# RPLidar_interface.net
KiCad netlist of a schematic drawn in EAGLE
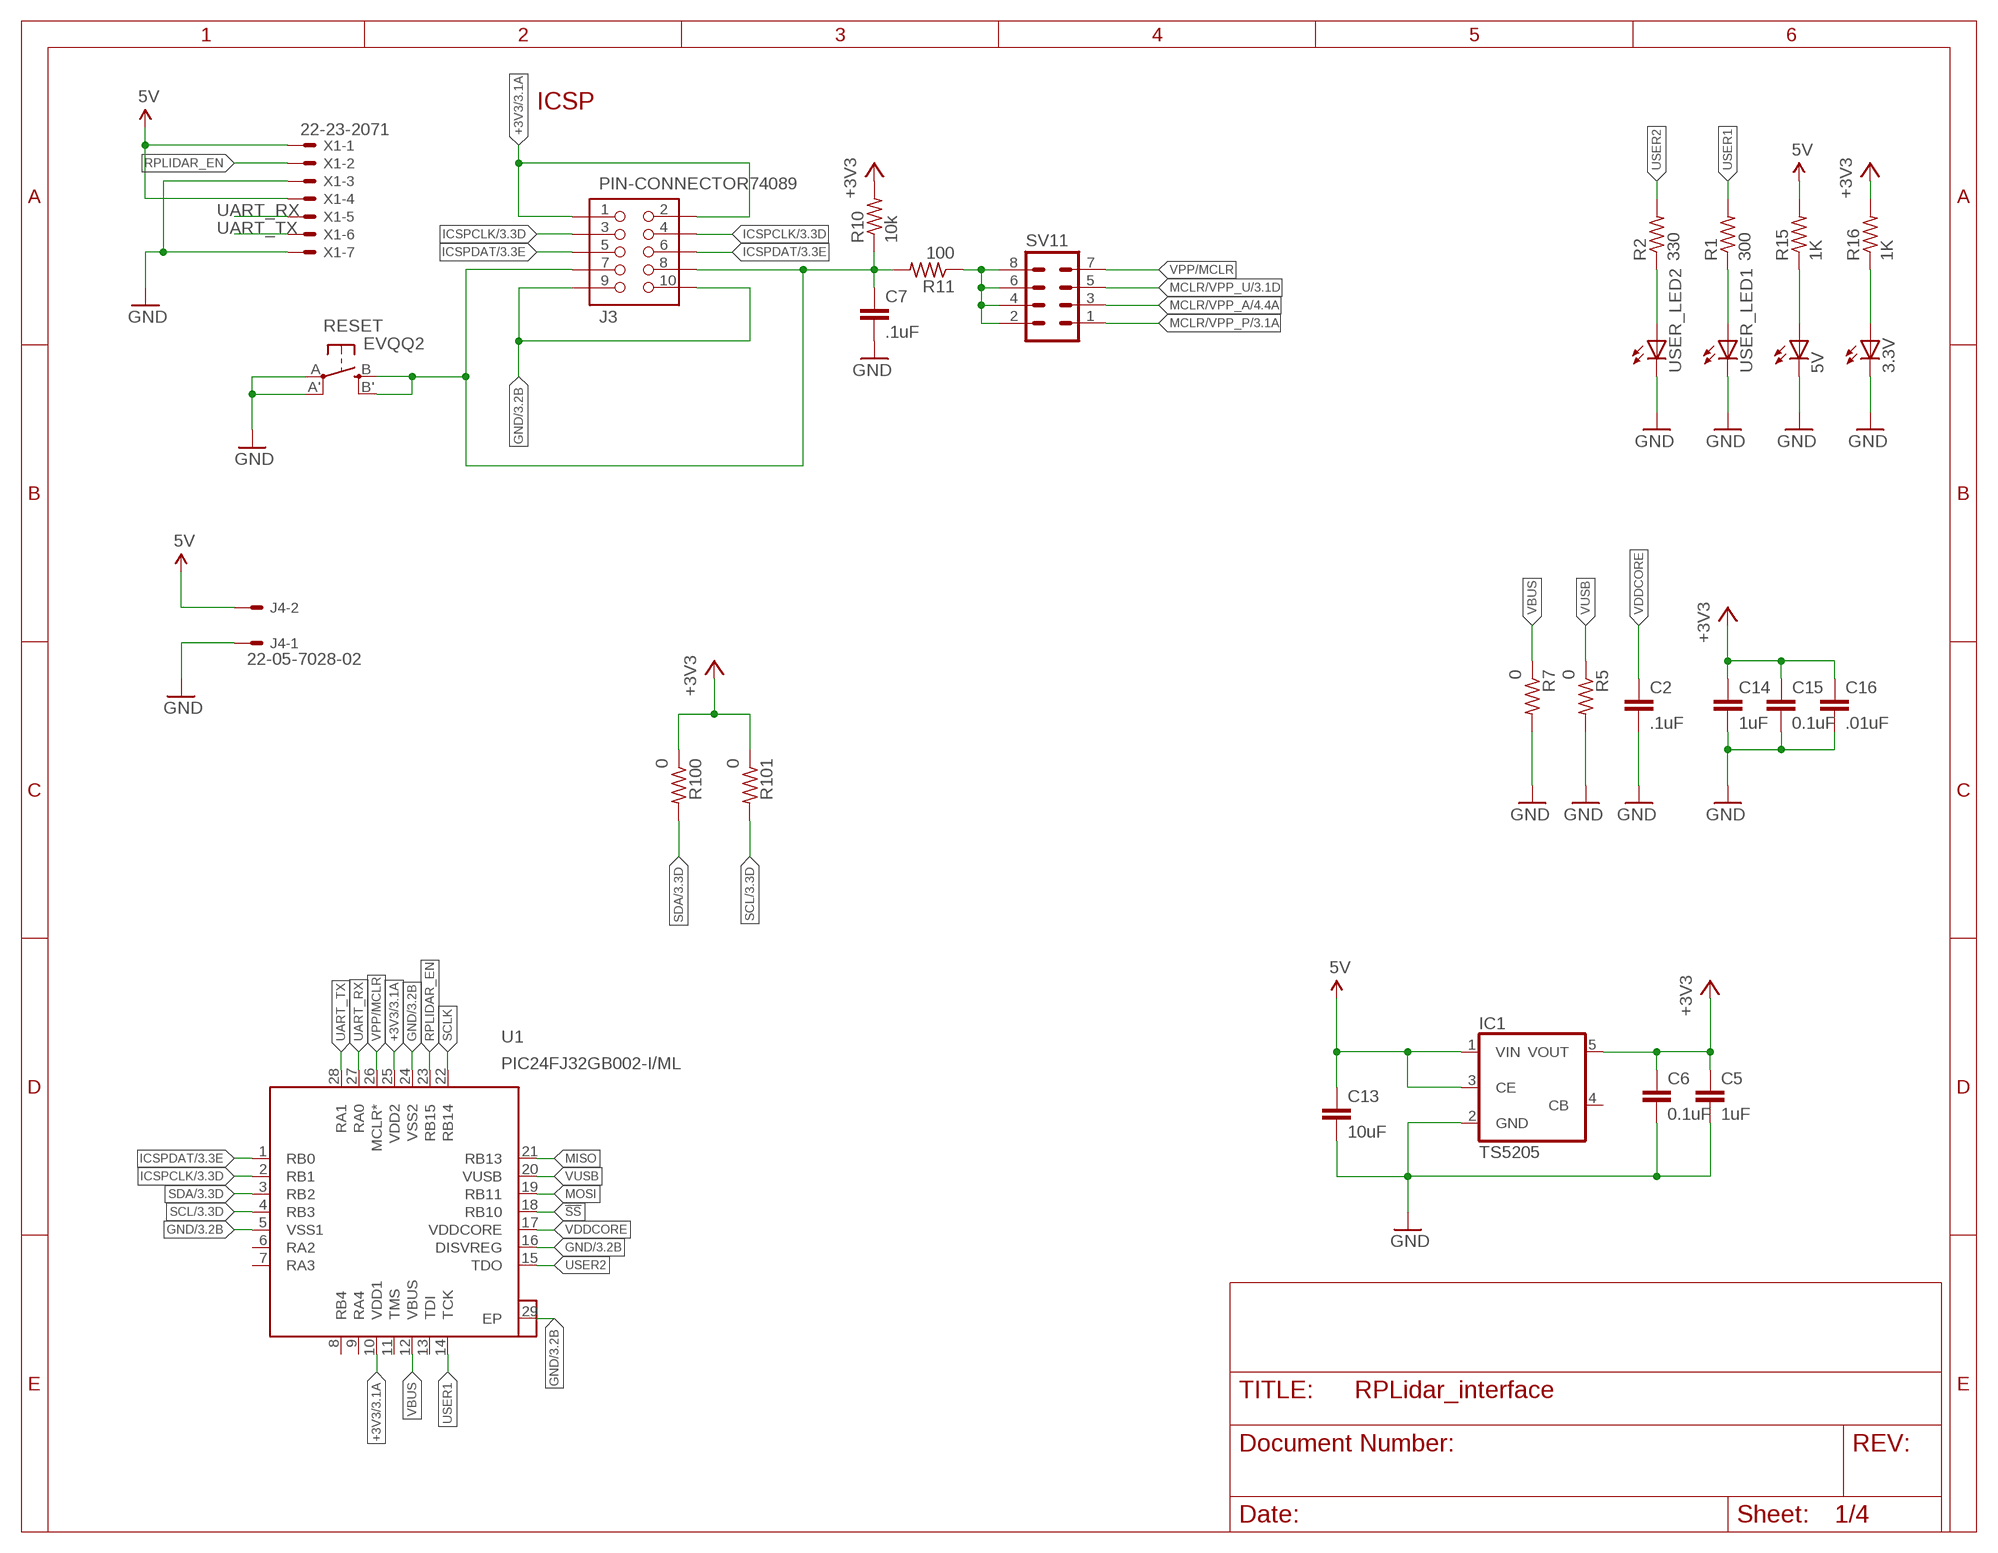
[diagram p0: schematic, sheet 1]
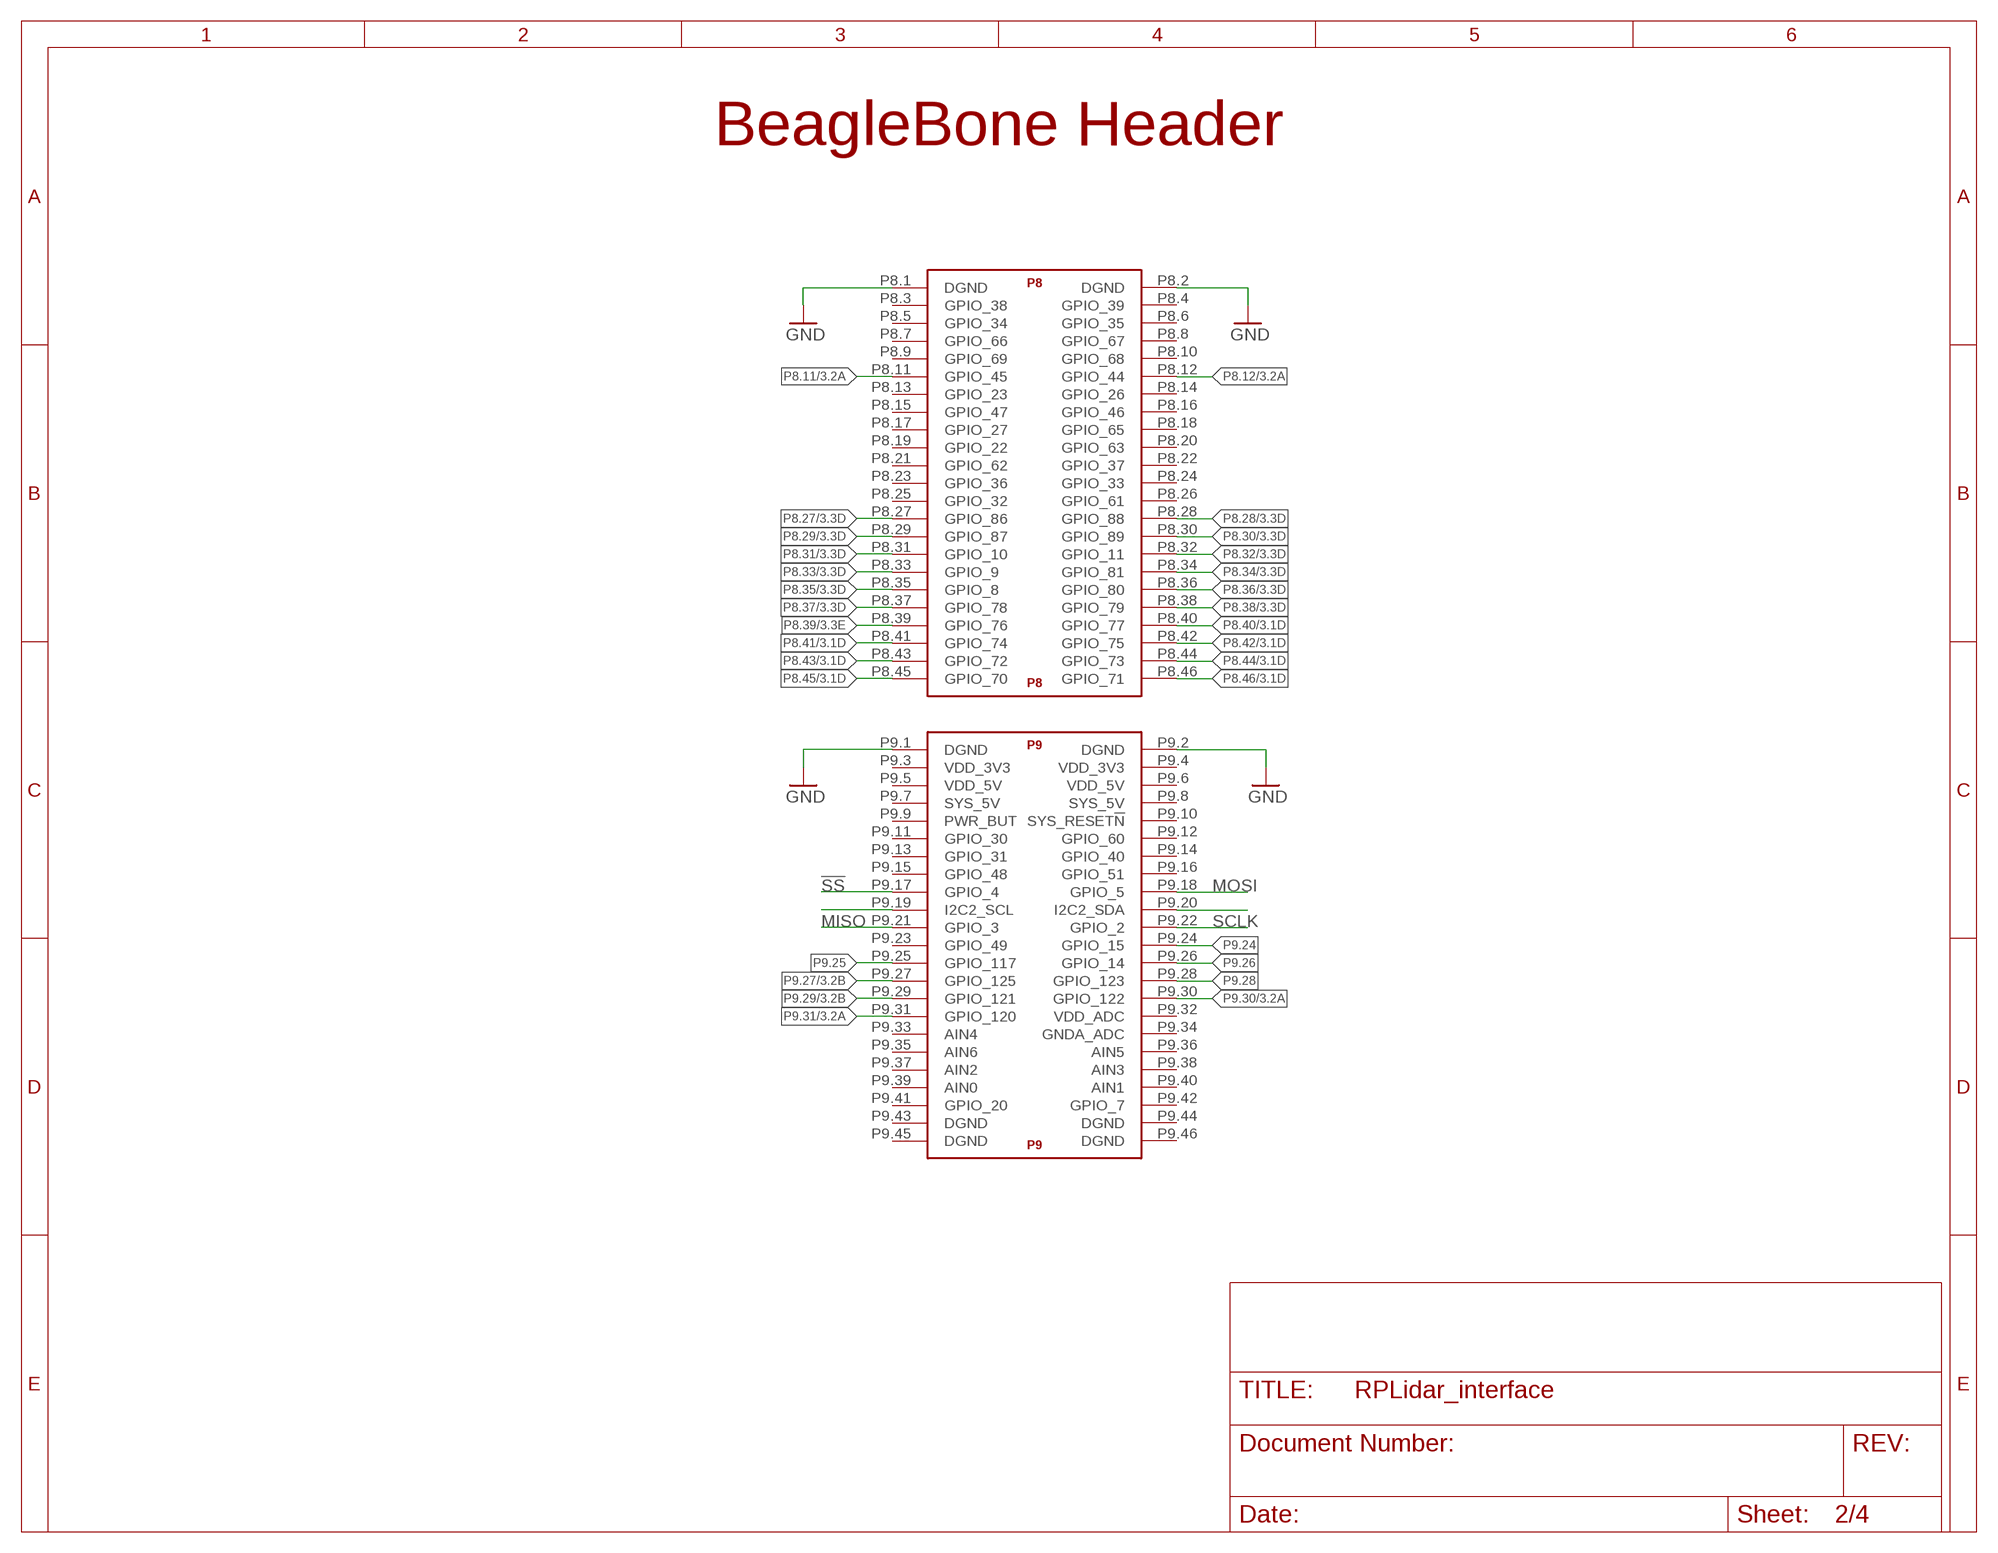
[diagram p1: schematic, sheet 2]
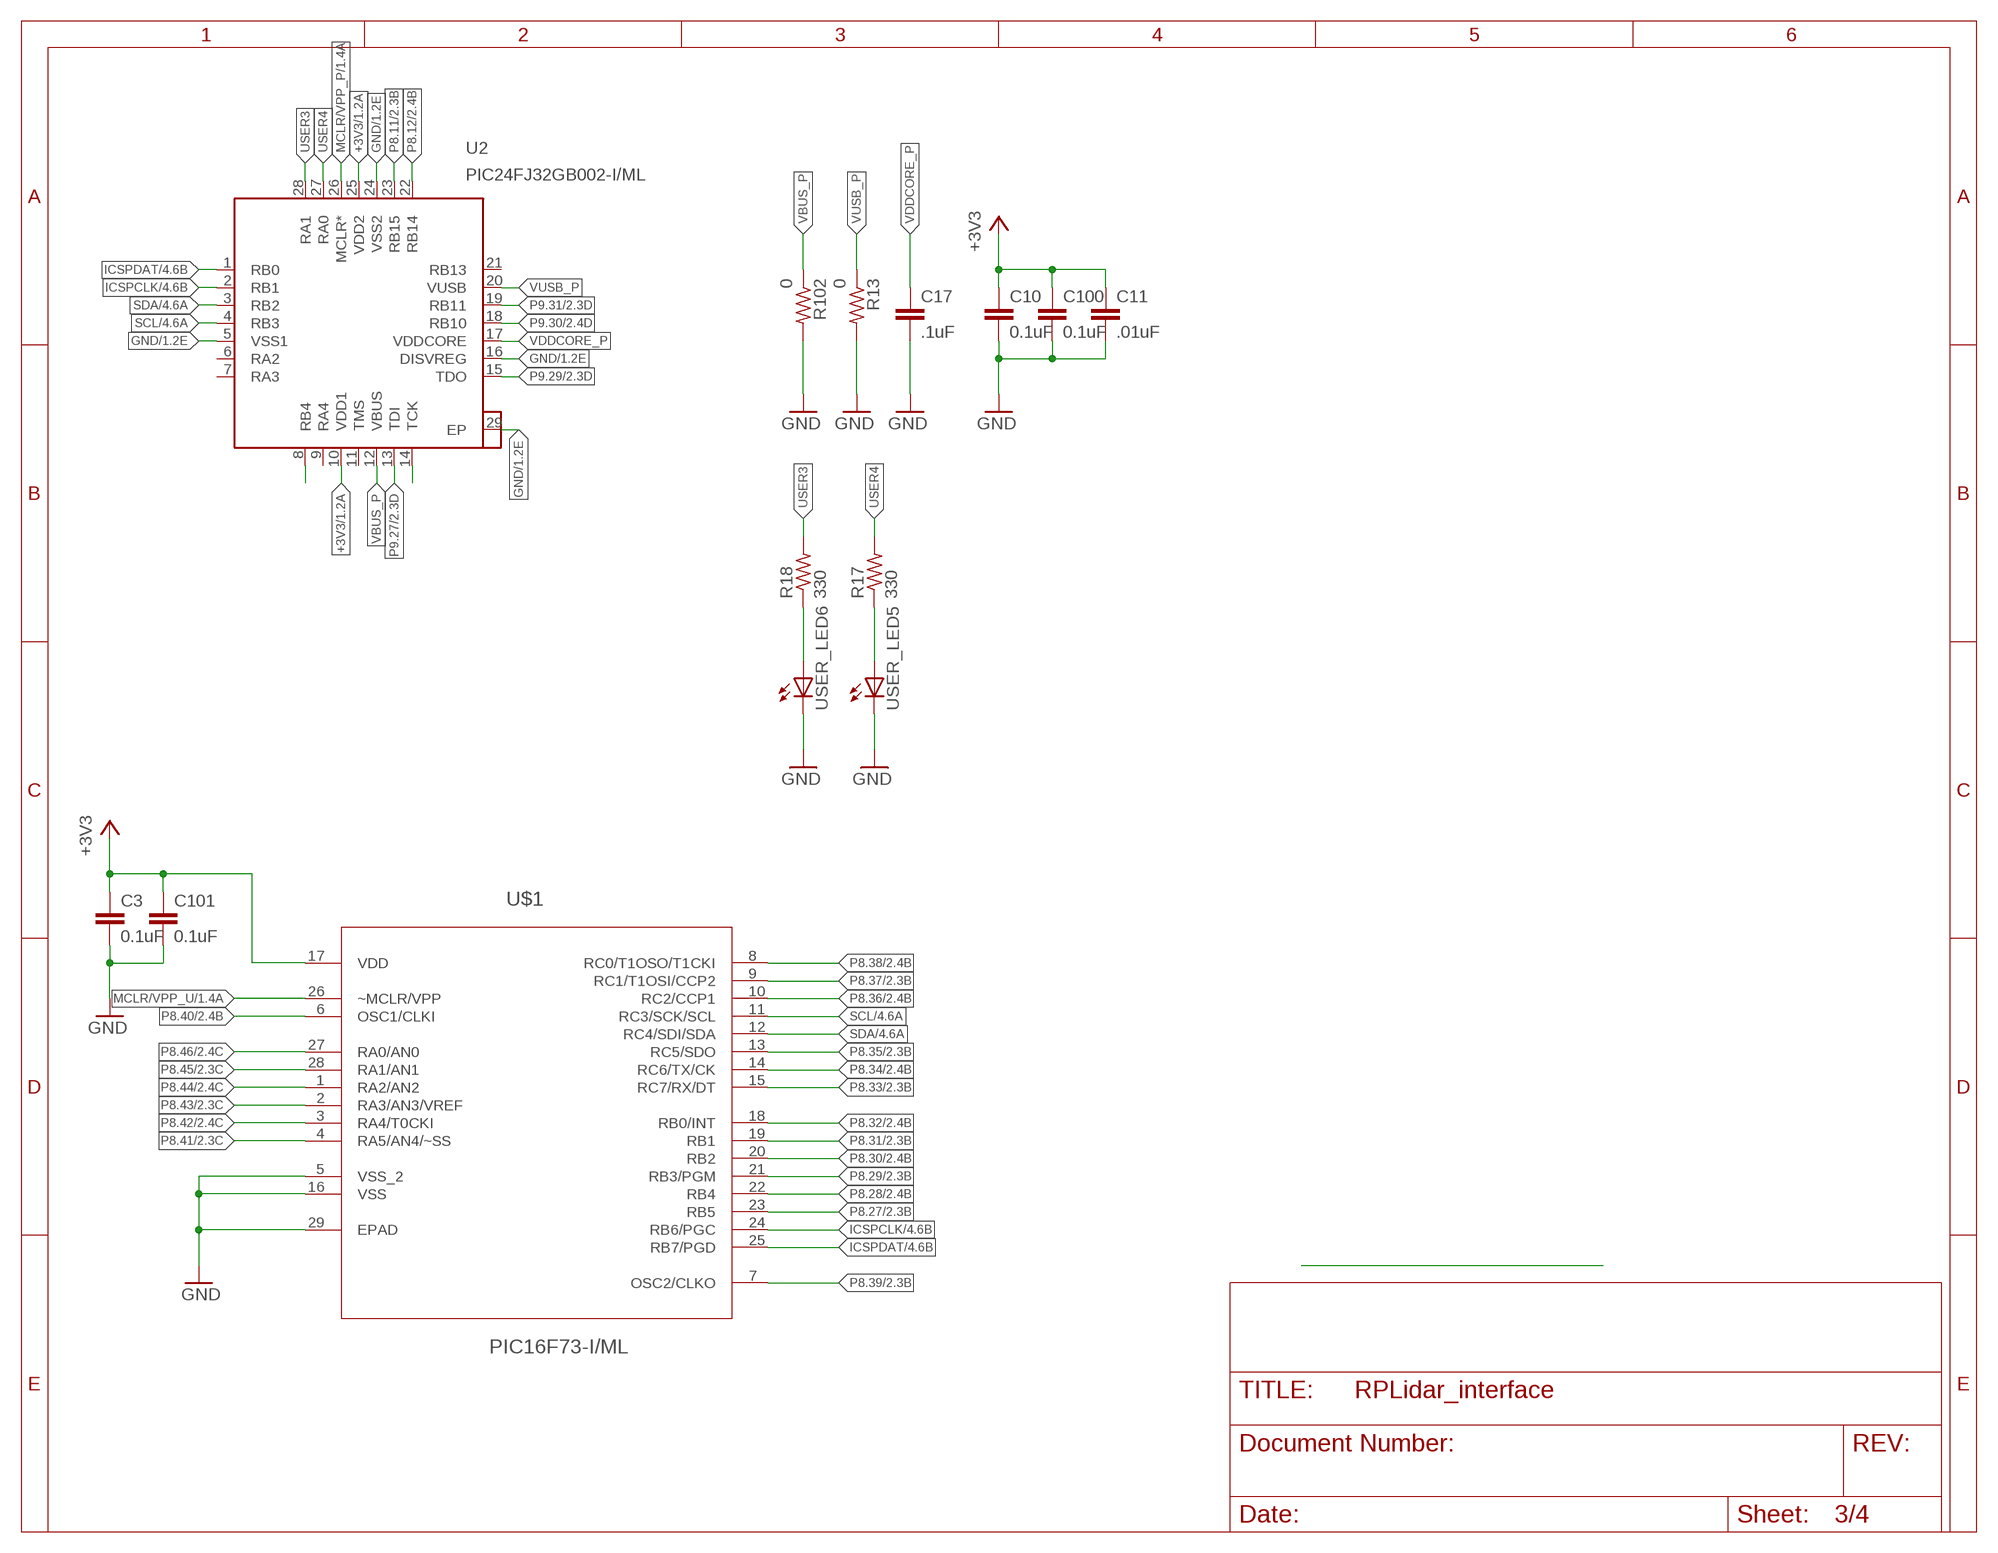
[diagram p2: schematic, sheet 3]
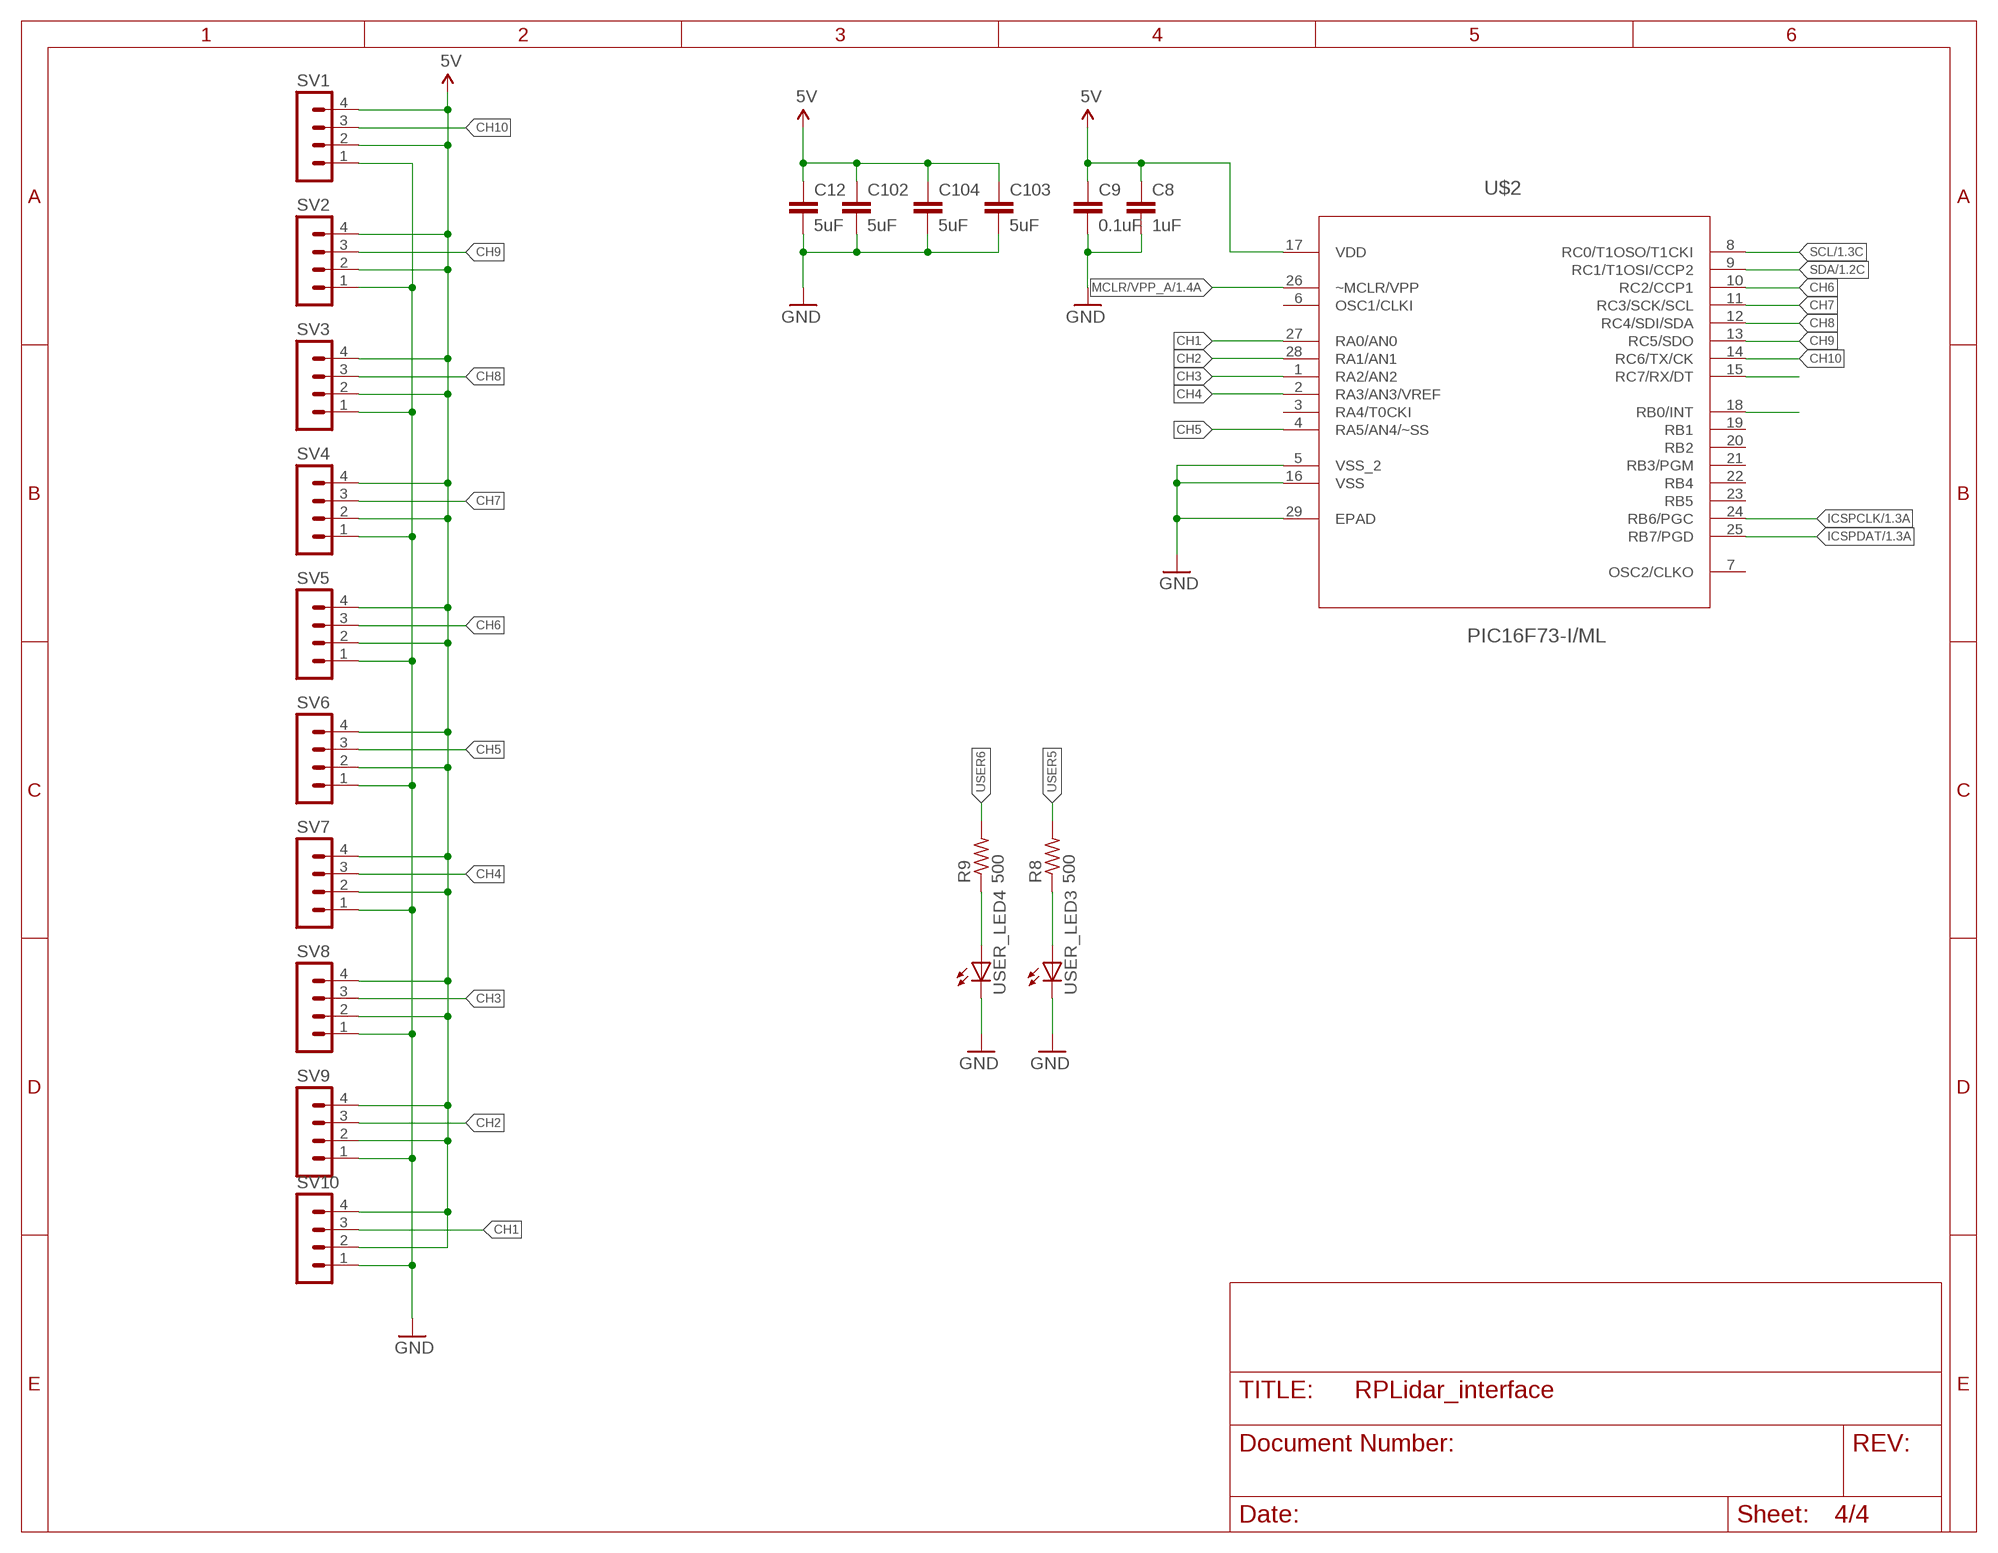
[diagram p3: schematic, sheet 4]

(export (version "E")
  (design (tool "Eeschema 10.0.6"))
  (components
    (comp (ref "C8")
      (value "1uF")
      (footprint "eagle-import:C0402")
      (libsource (lib "eagle-import") (part "C-EUC0402"))
    )
    (comp (ref "C9")
      (value "0.1uF")
      (footprint "eagle-import:C0402")
      (libsource (lib "eagle-import") (part "C-EUC0402"))
    )
    (comp (ref "C12")
      (value "5uF")
      (footprint "eagle-import:C0402")
      (libsource (lib "eagle-import") (part "C-EUC0402"))
    )
    (comp (ref "C102")
      (value "5uF")
      (footprint "eagle-import:C0402")
      (libsource (lib "eagle-import") (part "C-EUC0402"))
    )
    (comp (ref "C103")
      (value "5uF")
      (footprint "eagle-import:C0402")
      (libsource (lib "eagle-import") (part "C-EUC0402"))
    )
    (comp (ref "C104")
      (value "5uF")
      (footprint "eagle-import:C0402")
      (libsource (lib "eagle-import") (part "C-EUC0402"))
    )
    (comp (ref "R8")
      (value "500")
      (footprint "eagle-import:R0402")
      (libsource (lib "eagle-import") (part "R-US_R0402"))
    )
    (comp (ref "R9")
      (value "500")
      (footprint "eagle-import:R0402")
      (libsource (lib "eagle-import") (part "R-US_R0402"))
    )
    (comp (ref "SV1")
      (value "MA04-1")
      (footprint "eagle-import:MA04-1")
      (libsource (lib "eagle-import") (part "MA04-1"))
    )
    (comp (ref "SV2")
      (value "MA04-1")
      (footprint "eagle-import:MA04-1")
      (libsource (lib "eagle-import") (part "MA04-1"))
    )
    (comp (ref "SV3")
      (value "MA04-1")
      (footprint "eagle-import:MA04-1")
      (libsource (lib "eagle-import") (part "MA04-1"))
    )
    (comp (ref "SV4")
      (value "MA04-1")
      (footprint "eagle-import:MA04-1")
      (libsource (lib "eagle-import") (part "MA04-1"))
    )
    (comp (ref "SV5")
      (value "MA04-1")
      (footprint "eagle-import:MA04-1")
      (libsource (lib "eagle-import") (part "MA04-1"))
    )
    (comp (ref "SV6")
      (value "MA04-1")
      (footprint "eagle-import:MA04-1")
      (libsource (lib "eagle-import") (part "MA04-1"))
    )
    (comp (ref "SV7")
      (value "MA04-1")
      (footprint "eagle-import:MA04-1")
      (libsource (lib "eagle-import") (part "MA04-1"))
    )
    (comp (ref "SV8")
      (value "MA04-1")
      (footprint "eagle-import:MA04-1")
      (libsource (lib "eagle-import") (part "MA04-1"))
    )
    (comp (ref "SV9")
      (value "MA04-1")
      (footprint "eagle-import:MA04-1")
      (libsource (lib "eagle-import") (part "MA04-1"))
    )
    (comp (ref "SV10")
      (value "MA04-1")
      (footprint "eagle-import:MA04-1")
      (libsource (lib "eagle-import") (part "MA04-1"))
    )
    (comp (ref "U$2")
      (value "PIC16F73-I/ML")
      (footprint "eagle-import:QFN65P600X600X100-28N")
      (libsource (lib "eagle-import") (part "PIC16F73-I/ML"))
    )
    (comp (ref "USER_LED3")
      (value "LEDCHIP-LED0603")
      (footprint "eagle-import:CHIP-LED0603")
      (libsource (lib "eagle-import") (part "LEDCHIP-LED0603"))
    )
    (comp (ref "USER_LED4")
      (value "LEDCHIP-LED0603")
      (footprint "eagle-import:CHIP-LED0603")
      (libsource (lib "eagle-import") (part "LEDCHIP-LED0603"))
    )
    (comp (ref "C3")
      (value "0.1uF")
      (footprint "eagle-import:C0402")
      (libsource (lib "eagle-import") (part "C-EUC0402"))
    )
    (comp (ref "C10")
      (value "0.1uF")
      (footprint "eagle-import:C0402")
      (libsource (lib "eagle-import") (part "C-EUC0402"))
    )
    (comp (ref "C11")
      (value ".01uF")
      (footprint "eagle-import:C0402")
      (libsource (lib "eagle-import") (part "C-EUC0402"))
    )
    (comp (ref "C17")
      (value ".1uF")
      (footprint "eagle-import:C0402")
      (libsource (lib "eagle-import") (part "C-EUC0402"))
    )
    (comp (ref "C100")
      (value "0.1uF")
      (footprint "eagle-import:C0402")
      (libsource (lib "eagle-import") (part "C-EUC0402"))
    )
    (comp (ref "C101")
      (value "0.1uF")
      (footprint "eagle-import:C0402")
      (libsource (lib "eagle-import") (part "C-EUC0402"))
    )
    (comp (ref "R13")
      (value "0")
      (footprint "eagle-import:R0402")
      (libsource (lib "eagle-import") (part "R-US_R0402"))
    )
    (comp (ref "R17")
      (value "330")
      (footprint "eagle-import:R0402")
      (libsource (lib "eagle-import") (part "R-US_R0402"))
    )
    (comp (ref "R18")
      (value "330")
      (footprint "eagle-import:R0402")
      (libsource (lib "eagle-import") (part "R-US_R0402"))
    )
    (comp (ref "R102")
      (value "0")
      (footprint "eagle-import:R0402")
      (libsource (lib "eagle-import") (part "R-US_R0402"))
    )
    (comp (ref "U$1")
      (value "PIC16F73-I/ML")
      (footprint "eagle-import:QFN65P600X600X100-28N")
      (libsource (lib "eagle-import") (part "PIC16F73-I/ML"))
    )
    (comp (ref "U2")
      (value "PIC24FJ32GB002-I/ML")
      (footprint "eagle-import:QFN65P600X600X100-29N")
      (libsource (lib "eagle-import") (part "PIC24FJ32GB002-I/ML"))
    )
    (comp (ref "USER_LED5")
      (value "LEDCHIP-LED0603")
      (footprint "eagle-import:CHIP-LED0603")
      (libsource (lib "eagle-import") (part "LEDCHIP-LED0603"))
    )
    (comp (ref "USER_LED6")
      (value "LEDCHIP-LED0603")
      (footprint "eagle-import:CHIP-LED0603")
      (libsource (lib "eagle-import") (part "LEDCHIP-LED0603"))
    )
    (comp (ref "U$3")
      (value "BEAGLE_BONE_BLACK_CAPE")
      (footprint "eagle-import:BEAGLE_BONE_BLACK_CAPE")
      (libsource (lib "eagle-import") (part "BEAGLE_BONE_BLACK_CAPE"))
    )
    (comp (ref "3.3V")
      (value "LEDCHIP-LED0603")
      (footprint "eagle-import:CHIP-LED0603")
      (libsource (lib "eagle-import") (part "LEDCHIP-LED0603"))
    )
    (comp (ref "5V")
      (value "LEDCHIP-LED0603")
      (footprint "eagle-import:CHIP-LED0603")
      (libsource (lib "eagle-import") (part "LEDCHIP-LED0603"))
    )
    (comp (ref "C2")
      (value ".1uF")
      (footprint "eagle-import:C0402")
      (libsource (lib "eagle-import") (part "C-EUC0402"))
    )
    (comp (ref "C5")
      (value "1uF")
      (footprint "eagle-import:C0402")
      (libsource (lib "eagle-import") (part "C-EUC0402"))
    )
    (comp (ref "C6")
      (value "0.1uF")
      (footprint "eagle-import:C0402")
      (libsource (lib "eagle-import") (part "C-EUC0402"))
    )
    (comp (ref "C7")
      (value ".1uF")
      (footprint "eagle-import:C0402")
      (libsource (lib "eagle-import") (part "C-EUC0402"))
    )
    (comp (ref "C13")
      (value "10uF")
      (footprint "eagle-import:C0402")
      (libsource (lib "eagle-import") (part "C-EUC0402"))
    )
    (comp (ref "C14")
      (value "1uF")
      (footprint "eagle-import:C0402")
      (libsource (lib "eagle-import") (part "C-EUC0402"))
    )
    (comp (ref "C15")
      (value "0.1uF")
      (footprint "eagle-import:C0402")
      (libsource (lib "eagle-import") (part "C-EUC0402"))
    )
    (comp (ref "C16")
      (value ".01uF")
      (footprint "eagle-import:C0402")
      (libsource (lib "eagle-import") (part "C-EUC0402"))
    )
    (comp (ref "IC1")
      (value "TS5205")
      (footprint "eagle-import:SOT25")
      (libsource (lib "eagle-import") (part "TS5205"))
    )
    (comp (ref "J3")
      (value "PIN-CONNECTOR74089")
      (footprint "eagle-import:10-PIN-SMD")
      (libsource (lib "eagle-import") (part "PIN-CONNECTOR74089"))
    )
    (comp (ref "J4")
      (value "22-05-7028-02")
      (footprint "eagle-import:7395-02")
      (libsource (lib "eagle-import") (part "22-?-0205-7028"))
    )
    (comp (ref "R1")
      (value "300")
      (footprint "eagle-import:R0402")
      (libsource (lib "eagle-import") (part "R-US_R0402"))
    )
    (comp (ref "R2")
      (value "330")
      (footprint "eagle-import:R0402")
      (libsource (lib "eagle-import") (part "R-US_R0402"))
    )
    (comp (ref "R5")
      (value "0")
      (footprint "eagle-import:R0402")
      (libsource (lib "eagle-import") (part "R-US_R0402"))
    )
    (comp (ref "R7")
      (value "0")
      (footprint "eagle-import:R0402")
      (libsource (lib "eagle-import") (part "R-US_R0402"))
    )
    (comp (ref "R10")
      (value "10k")
      (footprint "eagle-import:R0402")
      (libsource (lib "eagle-import") (part "R-US_R0402"))
    )
    (comp (ref "R11")
      (value "100")
      (footprint "eagle-import:R0402")
      (libsource (lib "eagle-import") (part "R-US_R0402"))
    )
    (comp (ref "R15")
      (value "1K")
      (footprint "eagle-import:R0402")
      (libsource (lib "eagle-import") (part "R-US_R0402"))
    )
    (comp (ref "R16")
      (value "1K")
      (footprint "eagle-import:R0402")
      (libsource (lib "eagle-import") (part "R-US_R0402"))
    )
    (comp (ref "R100")
      (value "0")
      (footprint "eagle-import:R0402")
      (libsource (lib "eagle-import") (part "R-US_R0402"))
    )
    (comp (ref "R101")
      (value "0")
      (footprint "eagle-import:R0402")
      (libsource (lib "eagle-import") (part "R-US_R0402"))
    )
    (comp (ref "RESET")
      (value "EVQQ2")
      (footprint "eagle-import:EVQ-Q2")
      (libsource (lib "eagle-import") (part "EVQQ2"))
    )
    (comp (ref "SV11")
      (value "MA04-2")
      (footprint "eagle-import:MA04-2")
      (libsource (lib "eagle-import") (part "MA04-2"))
    )
    (comp (ref "U1")
      (value "PIC24FJ32GB002-I/ML")
      (footprint "eagle-import:QFN65P600X600X100-29N")
      (libsource (lib "eagle-import") (part "PIC24FJ32GB002-I/ML"))
    )
    (comp (ref "USER_LED1")
      (value "LEDCHIP-LED0603")
      (footprint "eagle-import:CHIP-LED0603")
      (libsource (lib "eagle-import") (part "LEDCHIP-LED0603"))
    )
    (comp (ref "USER_LED2")
      (value "LEDCHIP-LED0603")
      (footprint "eagle-import:CHIP-LED0603")
      (libsource (lib "eagle-import") (part "LEDCHIP-LED0603"))
    )
    (comp (ref "X1")
      (value "22-23-2071")
      (footprint "eagle-import:22-23-2071")
      (fields (field (name "MF") "MOLEX"))
      (libsource (lib "eagle-import") (part "22-23-2071"))
    )
  )
  (nets
    (net (code "1") (name "+3V3") (class "Default")
      (node (ref "C10") (pin "1") (pinfunction "1_1") (pintype "passive"))
      (node (ref "C100") (pin "1") (pinfunction "1_1") (pintype "passive"))
      (node (ref "C101") (pin "1") (pinfunction "1_1") (pintype "passive"))
      (node (ref "C11") (pin "1") (pinfunction "1_1") (pintype "passive"))
      (node (ref "C14") (pin "1") (pinfunction "1_1") (pintype "passive"))
      (node (ref "C15") (pin "1") (pinfunction "1_1") (pintype "passive"))
      (node (ref "C16") (pin "1") (pinfunction "1_1") (pintype "passive"))
      (node (ref "C3") (pin "1") (pinfunction "1_1") (pintype "passive"))
      (node (ref "C5") (pin "1") (pinfunction "1_1") (pintype "passive"))
      (node (ref "C6") (pin "1") (pinfunction "1_1") (pintype "passive"))
      (node (ref "IC1") (pin "5") (pinfunction "VOUT_5") (pintype "passive"))
      (node (ref "J3") (pin "1") (pinfunction "P$1_1") (pintype "power_in"))
      (node (ref "J3") (pin "2") (pinfunction "P$2_2") (pintype "power_in"))
      (node (ref "R10") (pin "2") (pinfunction "2_2") (pintype "passive"))
      (node (ref "R100") (pin "1") (pinfunction "1_1") (pintype "passive"))
      (node (ref "R101") (pin "1") (pinfunction "1_1") (pintype "passive"))
      (node (ref "R16") (pin "2") (pinfunction "2_2") (pintype "passive"))
      (node (ref "U$1") (pin "17") (pinfunction "VDD_17") (pintype "power_in"))
      (node (ref "U1") (pin "10") (pinfunction "VDD1_10") (pintype "power_in"))
      (node (ref "U1") (pin "25") (pinfunction "VDD2_25") (pintype "power_in"))
      (node (ref "U2") (pin "10") (pinfunction "VDD1_10") (pintype "power_in"))
      (node (ref "U2") (pin "25") (pinfunction "VDD2_25") (pintype "power_in"))
    )
    (net (code "2") (name "5V") (class "Default")
      (node (ref "C102") (pin "1") (pinfunction "1_1") (pintype "passive"))
      (node (ref "C103") (pin "1") (pinfunction "1_1") (pintype "passive"))
      (node (ref "C104") (pin "1") (pinfunction "1_1") (pintype "passive"))
      (node (ref "C12") (pin "1") (pinfunction "1_1") (pintype "passive"))
      (node (ref "C13") (pin "1") (pinfunction "1_1") (pintype "passive"))
      (node (ref "C8") (pin "1") (pinfunction "1_1") (pintype "passive"))
      (node (ref "C9") (pin "1") (pinfunction "1_1") (pintype "passive"))
      (node (ref "IC1") (pin "1") (pinfunction "VIN_1") (pintype "input"))
      (node (ref "IC1") (pin "3") (pinfunction "CE_3") (pintype "input"))
      (node (ref "J4") (pin "2") (pinfunction "S_2") (pintype "passive"))
      (node (ref "R15") (pin "2") (pinfunction "2_2") (pintype "passive"))
      (node (ref "SV1") (pin "2") (pinfunction "2_2") (pintype "passive"))
      (node (ref "SV1") (pin "4") (pinfunction "4_4") (pintype "passive"))
      (node (ref "SV10") (pin "2") (pinfunction "2_2") (pintype "passive"))
      (node (ref "SV10") (pin "4") (pinfunction "4_4") (pintype "passive"))
      (node (ref "SV2") (pin "2") (pinfunction "2_2") (pintype "passive"))
      (node (ref "SV2") (pin "4") (pinfunction "4_4") (pintype "passive"))
      (node (ref "SV3") (pin "2") (pinfunction "2_2") (pintype "passive"))
      (node (ref "SV3") (pin "4") (pinfunction "4_4") (pintype "passive"))
      (node (ref "SV4") (pin "2") (pinfunction "2_2") (pintype "passive"))
      (node (ref "SV4") (pin "4") (pinfunction "4_4") (pintype "passive"))
      (node (ref "SV5") (pin "2") (pinfunction "2_2") (pintype "passive"))
      (node (ref "SV5") (pin "4") (pinfunction "4_4") (pintype "passive"))
      (node (ref "SV6") (pin "2") (pinfunction "2_2") (pintype "passive"))
      (node (ref "SV6") (pin "4") (pinfunction "4_4") (pintype "passive"))
      (node (ref "SV7") (pin "2") (pinfunction "2_2") (pintype "passive"))
      (node (ref "SV7") (pin "4") (pinfunction "4_4") (pintype "passive"))
      (node (ref "SV8") (pin "2") (pinfunction "2_2") (pintype "passive"))
      (node (ref "SV8") (pin "4") (pinfunction "4_4") (pintype "passive"))
      (node (ref "SV9") (pin "2") (pinfunction "2_2") (pintype "passive"))
      (node (ref "SV9") (pin "4") (pinfunction "4_4") (pintype "passive"))
      (node (ref "U$2") (pin "17") (pinfunction "VDD_17") (pintype "power_in"))
      (node (ref "X1") (pin "1") (pinfunction "S_1") (pintype "passive"))
      (node (ref "X1") (pin "4") (pinfunction "S_4") (pintype "passive"))
    )
    (net (code "3") (name "CH1") (class "Default")
      (node (ref "SV10") (pin "3") (pinfunction "3_3") (pintype "passive"))
      (node (ref "U$2") (pin "27") (pinfunction "RA0/AN0_27") (pintype "bidirectional"))
    )
    (net (code "4") (name "CH2") (class "Default")
      (node (ref "SV9") (pin "3") (pinfunction "3_3") (pintype "passive"))
      (node (ref "U$2") (pin "28") (pinfunction "RA1/AN1_28") (pintype "bidirectional"))
    )
    (net (code "5") (name "CH3") (class "Default")
      (node (ref "SV8") (pin "3") (pinfunction "3_3") (pintype "passive"))
      (node (ref "U$2") (pin "1") (pinfunction "RA2/AN2_1") (pintype "bidirectional"))
    )
    (net (code "6") (name "CH4") (class "Default")
      (node (ref "SV7") (pin "3") (pinfunction "3_3") (pintype "passive"))
      (node (ref "U$2") (pin "2") (pinfunction "RA3/AN3/VREF_2") (pintype "bidirectional"))
    )
    (net (code "7") (name "CH5") (class "Default")
      (node (ref "SV6") (pin "3") (pinfunction "3_3") (pintype "passive"))
      (node (ref "U$2") (pin "4") (pinfunction "RA5/AN4/~{SS}_4") (pintype "bidirectional"))
    )
    (net (code "8") (name "CH6") (class "Default")
      (node (ref "SV5") (pin "3") (pinfunction "3_3") (pintype "passive"))
      (node (ref "U$2") (pin "10") (pinfunction "RC2/CCP1_10") (pintype "bidirectional"))
    )
    (net (code "9") (name "CH7") (class "Default")
      (node (ref "SV4") (pin "3") (pinfunction "3_3") (pintype "passive"))
      (node (ref "U$2") (pin "11") (pinfunction "RC3/SCK/SCL_11") (pintype "bidirectional"))
    )
    (net (code "10") (name "CH8") (class "Default")
      (node (ref "SV3") (pin "3") (pinfunction "3_3") (pintype "passive"))
      (node (ref "U$2") (pin "12") (pinfunction "RC4/SDI/SDA_12") (pintype "bidirectional"))
    )
    (net (code "11") (name "CH9") (class "Default")
      (node (ref "SV2") (pin "3") (pinfunction "3_3") (pintype "passive"))
      (node (ref "U$2") (pin "13") (pinfunction "RC5/SDO_13") (pintype "bidirectional"))
    )
    (net (code "12") (name "CH10") (class "Default")
      (node (ref "SV1") (pin "3") (pinfunction "3_3") (pintype "passive"))
      (node (ref "U$2") (pin "14") (pinfunction "RC6/TX/CK_14") (pintype "bidirectional"))
    )
    (net (code "13") (name "GND") (class "Default")
      (node (ref "3.3V") (pin "C") (pinfunction "C_C") (pintype "passive"))
      (node (ref "5V") (pin "C") (pinfunction "C_C") (pintype "passive"))
      (node (ref "C10") (pin "2") (pinfunction "2_2") (pintype "passive"))
      (node (ref "C100") (pin "2") (pinfunction "2_2") (pintype "passive"))
      (node (ref "C101") (pin "2") (pinfunction "2_2") (pintype "passive"))
      (node (ref "C102") (pin "2") (pinfunction "2_2") (pintype "passive"))
      (node (ref "C103") (pin "2") (pinfunction "2_2") (pintype "passive"))
      (node (ref "C104") (pin "2") (pinfunction "2_2") (pintype "passive"))
      (node (ref "C11") (pin "2") (pinfunction "2_2") (pintype "passive"))
      (node (ref "C12") (pin "2") (pinfunction "2_2") (pintype "passive"))
      (node (ref "C13") (pin "2") (pinfunction "2_2") (pintype "passive"))
      (node (ref "C14") (pin "2") (pinfunction "2_2") (pintype "passive"))
      (node (ref "C15") (pin "2") (pinfunction "2_2") (pintype "passive"))
      (node (ref "C16") (pin "2") (pinfunction "2_2") (pintype "passive"))
      (node (ref "C17") (pin "2") (pinfunction "2_2") (pintype "passive"))
      (node (ref "C2") (pin "2") (pinfunction "2_2") (pintype "passive"))
      (node (ref "C3") (pin "2") (pinfunction "2_2") (pintype "passive"))
      (node (ref "C5") (pin "2") (pinfunction "2_2") (pintype "passive"))
      (node (ref "C6") (pin "2") (pinfunction "2_2") (pintype "passive"))
      (node (ref "C7") (pin "2") (pinfunction "2_2") (pintype "passive"))
      (node (ref "C8") (pin "2") (pinfunction "2_2") (pintype "passive"))
      (node (ref "C9") (pin "2") (pinfunction "2_2") (pintype "passive"))
      (node (ref "IC1") (pin "2") (pinfunction "GND_2") (pintype "passive"))
      (node (ref "J3") (pin "10") (pinfunction "P$10_10") (pintype "power_in"))
      (node (ref "J3") (pin "9") (pinfunction "P$9_9") (pintype "power_in"))
      (node (ref "J4") (pin "1") (pinfunction "S_1") (pintype "passive"))
      (node (ref "R102") (pin "2") (pinfunction "2_2") (pintype "passive"))
      (node (ref "R13") (pin "2") (pinfunction "2_2") (pintype "passive"))
      (node (ref "R5") (pin "2") (pinfunction "2_2") (pintype "passive"))
      (node (ref "R7") (pin "2") (pinfunction "2_2") (pintype "passive"))
      (node (ref "RESET") (pin "A") (pinfunction "P_A") (pintype "passive"))
      (node (ref "RESET") (pin "A'") (pinfunction "P1_A'") (pintype "passive"))
      (node (ref "SV1") (pin "1") (pinfunction "1_1") (pintype "passive"))
      (node (ref "SV10") (pin "1") (pinfunction "1_1") (pintype "passive"))
      (node (ref "SV2") (pin "1") (pinfunction "1_1") (pintype "passive"))
      (node (ref "SV3") (pin "1") (pinfunction "1_1") (pintype "passive"))
      (node (ref "SV4") (pin "1") (pinfunction "1_1") (pintype "passive"))
      (node (ref "SV5") (pin "1") (pinfunction "1_1") (pintype "passive"))
      (node (ref "SV6") (pin "1") (pinfunction "1_1") (pintype "passive"))
      (node (ref "SV7") (pin "1") (pinfunction "1_1") (pintype "passive"))
      (node (ref "SV8") (pin "1") (pinfunction "1_1") (pintype "passive"))
      (node (ref "SV9") (pin "1") (pinfunction "1_1") (pintype "passive"))
      (node (ref "U$1") (pin "16") (pinfunction "VSS_16") (pintype "power_in"))
      (node (ref "U$1") (pin "29") (pinfunction "EPAD_29") (pintype "passive"))
      (node (ref "U$1") (pin "5") (pinfunction "VSS_2_5") (pintype "power_in"))
      (node (ref "U$2") (pin "16") (pinfunction "VSS_16") (pintype "power_in"))
      (node (ref "U$2") (pin "29") (pinfunction "EPAD_29") (pintype "passive"))
      (node (ref "U$2") (pin "5") (pinfunction "VSS_2_5") (pintype "power_in"))
      (node (ref "U$3") (pin "P8.1") (pinfunction "DGND_P8.1") (pintype "bidirectional"))
      (node (ref "U$3") (pin "P8.2") (pinfunction "DGND_P8.2") (pintype "bidirectional"))
      (node (ref "U$3") (pin "P9.1") (pinfunction "DGND_P9.1") (pintype "bidirectional"))
      (node (ref "U$3") (pin "P9.2") (pinfunction "DGND_P9.2") (pintype "bidirectional"))
      (node (ref "U1") (pin "16") (pinfunction "DISVREG_16") (pintype "passive"))
      (node (ref "U1") (pin "24") (pinfunction "VSS2_24") (pintype "power_in"))
      (node (ref "U1") (pin "29") (pinfunction "EP_29") (pintype "power_in"))
      (node (ref "U1") (pin "5") (pinfunction "VSS1_5") (pintype "power_in"))
      (node (ref "U2") (pin "16") (pinfunction "DISVREG_16") (pintype "passive"))
      (node (ref "U2") (pin "24") (pinfunction "VSS2_24") (pintype "power_in"))
      (node (ref "U2") (pin "29") (pinfunction "EP_29") (pintype "power_in"))
      (node (ref "U2") (pin "5") (pinfunction "VSS1_5") (pintype "power_in"))
      (node (ref "USER_LED1") (pin "C") (pinfunction "C_C") (pintype "passive"))
      (node (ref "USER_LED2") (pin "C") (pinfunction "C_C") (pintype "passive"))
      (node (ref "USER_LED3") (pin "C") (pinfunction "C_C") (pintype "passive"))
      (node (ref "USER_LED4") (pin "C") (pinfunction "C_C") (pintype "passive"))
      (node (ref "USER_LED5") (pin "C") (pinfunction "C_C") (pintype "passive"))
      (node (ref "USER_LED6") (pin "C") (pinfunction "C_C") (pintype "passive"))
      (node (ref "X1") (pin "3") (pinfunction "S_3") (pintype "passive"))
      (node (ref "X1") (pin "7") (pinfunction "S_7") (pintype "passive"))
    )
    (net (code "14") (name "ICSPCLK") (class "Default")
      (node (ref "J3") (pin "3") (pinfunction "P$3_3") (pintype "power_in"))
      (node (ref "J3") (pin "4") (pinfunction "P$4_4") (pintype "power_in"))
      (node (ref "U$1") (pin "24") (pinfunction "RB6/PGC_24") (pintype "bidirectional"))
      (node (ref "U$2") (pin "24") (pinfunction "RB6/PGC_24") (pintype "bidirectional"))
      (node (ref "U1") (pin "2") (pinfunction "RB1_2") (pintype "bidirectional"))
      (node (ref "U2") (pin "2") (pinfunction "RB1_2") (pintype "bidirectional"))
    )
    (net (code "15") (name "ICSPDAT") (class "Default")
      (node (ref "J3") (pin "5") (pinfunction "P$5_5") (pintype "power_in"))
      (node (ref "J3") (pin "6") (pinfunction "P$6_6") (pintype "power_in"))
      (node (ref "U$1") (pin "25") (pinfunction "RB7/PGD_25") (pintype "bidirectional"))
      (node (ref "U$2") (pin "25") (pinfunction "RB7/PGD_25") (pintype "bidirectional"))
      (node (ref "U1") (pin "1") (pinfunction "RB0_1") (pintype "bidirectional"))
      (node (ref "U2") (pin "1") (pinfunction "RB0_1") (pintype "bidirectional"))
    )
    (net (code "16") (name "MCLR{slash}VPP_A") (class "Default")
      (node (ref "SV11") (pin "3") (pinfunction "3_3") (pintype "passive"))
      (node (ref "U$2") (pin "26") (pinfunction "~{MCLR/VPP}_26") (pintype "input"))
    )
    (net (code "17") (name "MCLR{slash}VPP_P") (class "Default")
      (node (ref "SV11") (pin "1") (pinfunction "1_1") (pintype "passive"))
      (node (ref "U2") (pin "26") (pinfunction "MCLR*_26") (pintype "bidirectional"))
    )
    (net (code "18") (name "MCLR{slash}VPP_U") (class "Default")
      (node (ref "SV11") (pin "5") (pinfunction "5_5") (pintype "passive"))
      (node (ref "U$1") (pin "26") (pinfunction "~{MCLR/VPP}_26") (pintype "input"))
    )
    (net (code "19") (name "MISO") (class "Default")
      (node (ref "U$3") (pin "P9.21") (pinfunction "GPIO_3_P9.21") (pintype "bidirectional"))
      (node (ref "U1") (pin "21") (pinfunction "RB13_21") (pintype "bidirectional"))
    )
    (net (code "20") (name "MOSI") (class "Default")
      (node (ref "U$3") (pin "P9.18") (pinfunction "GPIO_5_P9.18") (pintype "bidirectional"))
      (node (ref "U1") (pin "19") (pinfunction "RB11_19") (pintype "passive"))
    )
    (net (code "21") (name "Net-(3.3V-PadA)") (class "Default")
      (node (ref "3.3V") (pin "A") (pinfunction "A_A") (pintype "passive"))
      (node (ref "R16") (pin "1") (pinfunction "1_1") (pintype "passive"))
    )
    (net (code "22") (name "Net-(5V-PadA)") (class "Default")
      (node (ref "5V") (pin "A") (pinfunction "A_A") (pintype "passive"))
      (node (ref "R15") (pin "1") (pinfunction "1_1") (pintype "passive"))
    )
    (net (code "23") (name "Net-(J3-P$7)") (class "Default")
      (node (ref "C7") (pin "1") (pinfunction "1_1") (pintype "passive"))
      (node (ref "J3") (pin "7") (pinfunction "P$7_7") (pintype "power_in"))
      (node (ref "J3") (pin "8") (pinfunction "P$8_8") (pintype "power_in"))
      (node (ref "R10") (pin "1") (pinfunction "1_1") (pintype "passive"))
      (node (ref "R11") (pin "2") (pinfunction "2_2") (pintype "passive"))
      (node (ref "RESET") (pin "B") (pinfunction "S_B") (pintype "passive"))
      (node (ref "RESET") (pin "B'") (pinfunction "S1_B'") (pintype "passive"))
    )
    (net (code "24") (name "Net-(R1-Pad1)") (class "Default")
      (node (ref "R1") (pin "1") (pinfunction "1_1") (pintype "passive"))
      (node (ref "USER_LED1") (pin "A") (pinfunction "A_A") (pintype "passive"))
    )
    (net (code "25") (name "Net-(R2-Pad1)") (class "Default")
      (node (ref "R2") (pin "1") (pinfunction "1_1") (pintype "passive"))
      (node (ref "USER_LED2") (pin "A") (pinfunction "A_A") (pintype "passive"))
    )
    (net (code "26") (name "Net-(R8-Pad1)") (class "Default")
      (node (ref "R8") (pin "1") (pinfunction "1_1") (pintype "passive"))
      (node (ref "USER_LED3") (pin "A") (pinfunction "A_A") (pintype "passive"))
    )
    (net (code "27") (name "Net-(R9-Pad1)") (class "Default")
      (node (ref "R9") (pin "1") (pinfunction "1_1") (pintype "passive"))
      (node (ref "USER_LED4") (pin "A") (pinfunction "A_A") (pintype "passive"))
    )
    (net (code "28") (name "Net-(R11-Pad1)") (class "Default")
      (node (ref "R11") (pin "1") (pinfunction "1_1") (pintype "passive"))
      (node (ref "SV11") (pin "2") (pinfunction "2_2") (pintype "passive"))
      (node (ref "SV11") (pin "4") (pinfunction "4_4") (pintype "passive"))
      (node (ref "SV11") (pin "6") (pinfunction "6_6") (pintype "passive"))
      (node (ref "SV11") (pin "8") (pinfunction "8_8") (pintype "passive"))
    )
    (net (code "29") (name "Net-(R17-Pad1)") (class "Default")
      (node (ref "R17") (pin "1") (pinfunction "1_1") (pintype "passive"))
      (node (ref "USER_LED5") (pin "A") (pinfunction "A_A") (pintype "passive"))
    )
    (net (code "30") (name "Net-(R18-Pad1)") (class "Default")
      (node (ref "R18") (pin "1") (pinfunction "1_1") (pintype "passive"))
      (node (ref "USER_LED6") (pin "A") (pinfunction "A_A") (pintype "passive"))
    )
    (net (code "31") (name "P8.11") (class "Default")
      (node (ref "U$3") (pin "P8.11") (pinfunction "GPIO_45_P8.11") (pintype "bidirectional"))
      (node (ref "U2") (pin "23") (pinfunction "RB15_23") (pintype "bidirectional"))
    )
    (net (code "32") (name "P8.12") (class "Default")
      (node (ref "U$3") (pin "P8.12") (pinfunction "GPIO_44_P8.12") (pintype "bidirectional"))
      (node (ref "U2") (pin "22") (pinfunction "RB14_22") (pintype "bidirectional"))
    )
    (net (code "33") (name "P8.27") (class "Default")
      (node (ref "U$1") (pin "23") (pinfunction "RB5_23") (pintype "bidirectional"))
      (node (ref "U$3") (pin "P8.27") (pinfunction "GPIO_86_P8.27") (pintype "bidirectional"))
    )
    (net (code "34") (name "P8.28") (class "Default")
      (node (ref "U$1") (pin "22") (pinfunction "RB4_22") (pintype "bidirectional"))
      (node (ref "U$3") (pin "P8.28") (pinfunction "GPIO_88_P8.28") (pintype "bidirectional"))
    )
    (net (code "35") (name "P8.29") (class "Default")
      (node (ref "U$1") (pin "21") (pinfunction "RB3/PGM_21") (pintype "bidirectional"))
      (node (ref "U$3") (pin "P8.29") (pinfunction "GPIO_87_P8.29") (pintype "bidirectional"))
    )
    (net (code "36") (name "P8.30") (class "Default")
      (node (ref "U$1") (pin "20") (pinfunction "RB2_20") (pintype "bidirectional"))
      (node (ref "U$3") (pin "P8.30") (pinfunction "GPIO_89_P8.30") (pintype "bidirectional"))
    )
    (net (code "37") (name "P8.31") (class "Default")
      (node (ref "U$1") (pin "19") (pinfunction "RB1_19") (pintype "bidirectional"))
      (node (ref "U$3") (pin "P8.31") (pinfunction "GPIO_10_P8.31") (pintype "bidirectional"))
    )
    (net (code "38") (name "P8.32") (class "Default")
      (node (ref "U$1") (pin "18") (pinfunction "RB0/INT_18") (pintype "bidirectional"))
      (node (ref "U$3") (pin "P8.32") (pinfunction "GPIO_11_P8.32") (pintype "bidirectional"))
    )
    (net (code "39") (name "P8.33") (class "Default")
      (node (ref "U$1") (pin "15") (pinfunction "RC7/RX/DT_15") (pintype "bidirectional"))
      (node (ref "U$3") (pin "P8.33") (pinfunction "GPIO_9_P8.33") (pintype "bidirectional"))
    )
    (net (code "40") (name "P8.34") (class "Default")
      (node (ref "U$1") (pin "14") (pinfunction "RC6/TX/CK_14") (pintype "bidirectional"))
      (node (ref "U$3") (pin "P8.34") (pinfunction "GPIO_81_P8.34") (pintype "bidirectional"))
    )
    (net (code "41") (name "P8.35") (class "Default")
      (node (ref "U$1") (pin "13") (pinfunction "RC5/SDO_13") (pintype "bidirectional"))
      (node (ref "U$3") (pin "P8.35") (pinfunction "GPIO_8_P8.35") (pintype "bidirectional"))
    )
    (net (code "42") (name "P8.36") (class "Default")
      (node (ref "U$1") (pin "10") (pinfunction "RC2/CCP1_10") (pintype "bidirectional"))
      (node (ref "U$3") (pin "P8.36") (pinfunction "GPIO_80_P8.36") (pintype "bidirectional"))
    )
    (net (code "43") (name "P8.37") (class "Default")
      (node (ref "U$1") (pin "9") (pinfunction "RC1/T1OSI/CCP2_9") (pintype "bidirectional"))
      (node (ref "U$3") (pin "P8.37") (pinfunction "GPIO_78_P8.37") (pintype "bidirectional"))
    )
    (net (code "44") (name "P8.38") (class "Default")
      (node (ref "U$1") (pin "8") (pinfunction "RC0/T1OSO/T1CKI_8") (pintype "bidirectional"))
      (node (ref "U$3") (pin "P8.38") (pinfunction "GPIO_79_P8.38") (pintype "bidirectional"))
    )
    (net (code "45") (name "P8.39") (class "Default")
      (node (ref "U$1") (pin "7") (pinfunction "OSC2/CLKO_7") (pintype "output"))
      (node (ref "U$3") (pin "P8.39") (pinfunction "GPIO_76_P8.39") (pintype "bidirectional"))
    )
    (net (code "46") (name "P8.40") (class "Default")
      (node (ref "U$1") (pin "6") (pinfunction "OSC1/CLKI_6") (pintype "input"))
      (node (ref "U$3") (pin "P8.40") (pinfunction "GPIO_77_P8.40") (pintype "bidirectional"))
    )
    (net (code "47") (name "P8.41") (class "Default")
      (node (ref "U$1") (pin "4") (pinfunction "RA5/AN4/~{SS}_4") (pintype "bidirectional"))
      (node (ref "U$3") (pin "P8.41") (pinfunction "GPIO_74_P8.41") (pintype "bidirectional"))
    )
    (net (code "48") (name "P8.42") (class "Default")
      (node (ref "U$1") (pin "3") (pinfunction "RA4/T0CKI_3") (pintype "bidirectional"))
      (node (ref "U$3") (pin "P8.42") (pinfunction "GPIO_75_P8.42") (pintype "bidirectional"))
    )
    (net (code "49") (name "P8.43") (class "Default")
      (node (ref "U$1") (pin "2") (pinfunction "RA3/AN3/VREF_2") (pintype "bidirectional"))
      (node (ref "U$3") (pin "P8.43") (pinfunction "GPIO_72_P8.43") (pintype "bidirectional"))
    )
    (net (code "50") (name "P8.44") (class "Default")
      (node (ref "U$1") (pin "1") (pinfunction "RA2/AN2_1") (pintype "bidirectional"))
      (node (ref "U$3") (pin "P8.44") (pinfunction "GPIO_73_P8.44") (pintype "bidirectional"))
    )
    (net (code "51") (name "P8.45") (class "Default")
      (node (ref "U$1") (pin "28") (pinfunction "RA1/AN1_28") (pintype "bidirectional"))
      (node (ref "U$3") (pin "P8.45") (pinfunction "GPIO_70_P8.45") (pintype "bidirectional"))
    )
    (net (code "52") (name "P8.46") (class "Default")
      (node (ref "U$1") (pin "27") (pinfunction "RA0/AN0_27") (pintype "bidirectional"))
      (node (ref "U$3") (pin "P8.46") (pinfunction "GPIO_71_P8.46") (pintype "bidirectional"))
    )
    (net (code "53") (name "P9.24") (class "Default")
      (node (ref "U$3") (pin "P9.24") (pinfunction "GPIO_15_P9.24") (pintype "bidirectional"))
    )
    (net (code "54") (name "P9.25") (class "Default")
      (node (ref "U$3") (pin "P9.25") (pinfunction "GPIO_117_P9.25") (pintype "bidirectional"))
      (node (ref "U2") (pin "8") (pinfunction "RB4_8") (pintype "bidirectional"))
    )
    (net (code "55") (name "P9.26") (class "Default")
      (node (ref "U$3") (pin "P9.26") (pinfunction "GPIO_14_P9.26") (pintype "bidirectional"))
    )
    (net (code "56") (name "P9.27") (class "Default")
      (node (ref "U$3") (pin "P9.27") (pinfunction "GPIO_125_P9.27") (pintype "bidirectional"))
      (node (ref "U2") (pin "13") (pinfunction "TDI_13") (pintype "input"))
    )
    (net (code "57") (name "P9.28") (class "Default")
      (node (ref "U$3") (pin "P9.28") (pinfunction "GPIO_123_P9.28") (pintype "bidirectional"))
      (node (ref "U2") (pin "14") (pinfunction "TCK_14") (pintype "input"))
    )
    (net (code "58") (name "P9.29") (class "Default")
      (node (ref "U$3") (pin "P9.29") (pinfunction "GPIO_121_P9.29") (pintype "bidirectional"))
      (node (ref "U2") (pin "15") (pinfunction "TDO_15") (pintype "output"))
    )
    (net (code "59") (name "P9.30") (class "Default")
      (node (ref "U$3") (pin "P9.30") (pinfunction "GPIO_122_P9.30") (pintype "bidirectional"))
      (node (ref "U2") (pin "18") (pinfunction "RB10_18") (pintype "passive"))
    )
    (net (code "60") (name "P9.31") (class "Default")
      (node (ref "U$3") (pin "P9.31") (pinfunction "GPIO_120_P9.31") (pintype "bidirectional"))
      (node (ref "U2") (pin "19") (pinfunction "RB11_19") (pintype "passive"))
    )
    (net (code "61") (name "RPLIDAR_EN") (class "Default")
      (node (ref "U1") (pin "23") (pinfunction "RB15_23") (pintype "bidirectional"))
      (node (ref "X1") (pin "2") (pinfunction "S_2") (pintype "passive"))
    )
    (net (code "62") (name "SCL") (class "Default")
      (node (ref "R101") (pin "2") (pinfunction "2_2") (pintype "passive"))
      (node (ref "U$1") (pin "11") (pinfunction "RC3/SCK/SCL_11") (pintype "bidirectional"))
      (node (ref "U$2") (pin "8") (pinfunction "RC0/T1OSO/T1CKI_8") (pintype "bidirectional"))
      (node (ref "U$3") (pin "P9.19") (pinfunction "I2C2_SCL_P9.19") (pintype "bidirectional"))
      (node (ref "U1") (pin "4") (pinfunction "RB3_4") (pintype "bidirectional"))
      (node (ref "U2") (pin "4") (pinfunction "RB3_4") (pintype "bidirectional"))
    )
    (net (code "63") (name "SCLK") (class "Default")
      (node (ref "U$3") (pin "P9.22") (pinfunction "GPIO_2_P9.22") (pintype "bidirectional"))
      (node (ref "U1") (pin "22") (pinfunction "RB14_22") (pintype "bidirectional"))
    )
    (net (code "64") (name "SDA") (class "Default")
      (node (ref "R100") (pin "2") (pinfunction "2_2") (pintype "passive"))
      (node (ref "U$1") (pin "12") (pinfunction "RC4/SDI/SDA_12") (pintype "bidirectional"))
      (node (ref "U$2") (pin "9") (pinfunction "RC1/T1OSI/CCP2_9") (pintype "bidirectional"))
      (node (ref "U$3") (pin "P9.20") (pinfunction "I2C2_SDA_P9.20") (pintype "bidirectional"))
      (node (ref "U1") (pin "3") (pinfunction "RB2_3") (pintype "bidirectional"))
      (node (ref "U2") (pin "3") (pinfunction "RB2_3") (pintype "bidirectional"))
    )
    (net (code "65") (name "UART_RX") (class "Default")
      (node (ref "U1") (pin "27") (pinfunction "RA0_27") (pintype "bidirectional"))
      (node (ref "X1") (pin "5") (pinfunction "S_5") (pintype "passive"))
    )
    (net (code "66") (name "UART_TX") (class "Default")
      (node (ref "U1") (pin "28") (pinfunction "RA1_28") (pintype "bidirectional"))
      (node (ref "X1") (pin "6") (pinfunction "S_6") (pintype "passive"))
    )
    (net (code "67") (name "USER1") (class "Default")
      (node (ref "R1") (pin "2") (pinfunction "2_2") (pintype "passive"))
      (node (ref "U1") (pin "14") (pinfunction "TCK_14") (pintype "input"))
    )
    (net (code "68") (name "USER2") (class "Default")
      (node (ref "R2") (pin "2") (pinfunction "2_2") (pintype "passive"))
      (node (ref "U1") (pin "15") (pinfunction "TDO_15") (pintype "output"))
    )
    (net (code "69") (name "USER3") (class "Default")
      (node (ref "R18") (pin "2") (pinfunction "2_2") (pintype "passive"))
      (node (ref "U2") (pin "28") (pinfunction "RA1_28") (pintype "bidirectional"))
    )
    (net (code "70") (name "USER4") (class "Default")
      (node (ref "R17") (pin "2") (pinfunction "2_2") (pintype "passive"))
      (node (ref "U2") (pin "27") (pinfunction "RA0_27") (pintype "bidirectional"))
    )
    (net (code "71") (name "USER5") (class "Default")
      (node (ref "R8") (pin "2") (pinfunction "2_2") (pintype "passive"))
      (node (ref "U$2") (pin "15") (pinfunction "RC7/RX/DT_15") (pintype "bidirectional"))
    )
    (net (code "72") (name "USER6") (class "Default")
      (node (ref "R9") (pin "2") (pinfunction "2_2") (pintype "passive"))
      (node (ref "U$2") (pin "18") (pinfunction "RB0/INT_18") (pintype "bidirectional"))
    )
    (net (code "73") (name "VBUS") (class "Default")
      (node (ref "R7") (pin "1") (pinfunction "1_1") (pintype "passive"))
      (node (ref "U1") (pin "12") (pinfunction "VBUS_12") (pintype "passive"))
    )
    (net (code "74") (name "VBUS_P") (class "Default")
      (node (ref "R102") (pin "1") (pinfunction "1_1") (pintype "passive"))
      (node (ref "U2") (pin "12") (pinfunction "VBUS_12") (pintype "passive"))
    )
    (net (code "75") (name "VDDCORE") (class "Default")
      (node (ref "C2") (pin "1") (pinfunction "1_1") (pintype "passive"))
      (node (ref "U1") (pin "17") (pinfunction "VDDCORE_17") (pintype "power_in"))
    )
    (net (code "76") (name "VDDCORE_P") (class "Default")
      (node (ref "C17") (pin "1") (pinfunction "1_1") (pintype "passive"))
      (node (ref "U2") (pin "17") (pinfunction "VDDCORE_17") (pintype "power_in"))
    )
    (net (code "77") (name "VPP{slash}MCLR") (class "Default")
      (node (ref "SV11") (pin "7") (pinfunction "7_7") (pintype "passive"))
      (node (ref "U1") (pin "26") (pinfunction "MCLR*_26") (pintype "bidirectional"))
    )
    (net (code "78") (name "VUSB") (class "Default")
      (node (ref "R5") (pin "1") (pinfunction "1_1") (pintype "passive"))
      (node (ref "U1") (pin "20") (pinfunction "VUSB_20") (pintype "passive"))
    )
    (net (code "79") (name "VUSB_P") (class "Default")
      (node (ref "R13") (pin "1") (pinfunction "1_1") (pintype "passive"))
      (node (ref "U2") (pin "20") (pinfunction "VUSB_20") (pintype "passive"))
    )
    (net (code "80") (name "unconnected-(IC1-CB-Pad4)") (class "Default")
      (node (ref "IC1") (pin "4") (pinfunction "CB_4") (pintype "input"))
    )
    (net (code "81") (name "unconnected-(U$2-OSC1{slash}CLKI-Pad6)") (class "Default")
      (node (ref "U$2") (pin "6") (pinfunction "OSC1/CLKI_6") (pintype "input"))
    )
    (net (code "82") (name "unconnected-(U$2-OSC2{slash}CLKO-Pad7)") (class "Default")
      (node (ref "U$2") (pin "7") (pinfunction "OSC2/CLKO_7") (pintype "output"))
    )
    (net (code "83") (name "unconnected-(U$2-RA4{slash}T0CKI-Pad3)") (class "Default")
      (node (ref "U$2") (pin "3") (pinfunction "RA4/T0CKI_3") (pintype "bidirectional"))
    )
    (net (code "84") (name "unconnected-(U$2-RB1-Pad19)") (class "Default")
      (node (ref "U$2") (pin "19") (pinfunction "RB1_19") (pintype "bidirectional"))
    )
    (net (code "85") (name "unconnected-(U$2-RB2-Pad20)") (class "Default")
      (node (ref "U$2") (pin "20") (pinfunction "RB2_20") (pintype "bidirectional"))
    )
    (net (code "86") (name "unconnected-(U$2-RB3{slash}PGM-Pad21)") (class "Default")
      (node (ref "U$2") (pin "21") (pinfunction "RB3/PGM_21") (pintype "bidirectional"))
    )
    (net (code "87") (name "unconnected-(U$2-RB4-Pad22)") (class "Default")
      (node (ref "U$2") (pin "22") (pinfunction "RB4_22") (pintype "bidirectional"))
    )
    (net (code "88") (name "unconnected-(U$2-RB5-Pad23)") (class "Default")
      (node (ref "U$2") (pin "23") (pinfunction "RB5_23") (pintype "bidirectional"))
    )
    (net (code "89") (name "unconnected-(U$3A-GPIO_22-PadP8.19)") (class "Default")
      (node (ref "U$3") (pin "P8.19") (pinfunction "GPIO_22_P8.19") (pintype "bidirectional"))
    )
    (net (code "90") (name "unconnected-(U$3A-GPIO_23-PadP8.13)") (class "Default")
      (node (ref "U$3") (pin "P8.13") (pinfunction "GPIO_23_P8.13") (pintype "bidirectional"))
    )
    (net (code "91") (name "unconnected-(U$3A-GPIO_26-PadP8.14)") (class "Default")
      (node (ref "U$3") (pin "P8.14") (pinfunction "GPIO_26_P8.14") (pintype "bidirectional"))
    )
    (net (code "92") (name "unconnected-(U$3A-GPIO_27-PadP8.17)") (class "Default")
      (node (ref "U$3") (pin "P8.17") (pinfunction "GPIO_27_P8.17") (pintype "bidirectional"))
    )
    (net (code "93") (name "unconnected-(U$3A-GPIO_32-PadP8.25)") (class "Default")
      (node (ref "U$3") (pin "P8.25") (pinfunction "GPIO_32_P8.25") (pintype "bidirectional"))
    )
    (net (code "94") (name "unconnected-(U$3A-GPIO_33-PadP8.24)") (class "Default")
      (node (ref "U$3") (pin "P8.24") (pinfunction "GPIO_33_P8.24") (pintype "bidirectional"))
    )
    (net (code "95") (name "unconnected-(U$3A-GPIO_34-PadP8.5)") (class "Default")
      (node (ref "U$3") (pin "P8.5") (pinfunction "GPIO_34_P8.5") (pintype "bidirectional"))
    )
    (net (code "96") (name "unconnected-(U$3A-GPIO_35-PadP8.6)") (class "Default")
      (node (ref "U$3") (pin "P8.6") (pinfunction "GPIO_35_P8.6") (pintype "bidirectional"))
    )
    (net (code "97") (name "unconnected-(U$3A-GPIO_36-PadP8.23)") (class "Default")
      (node (ref "U$3") (pin "P8.23") (pinfunction "GPIO_36_P8.23") (pintype "bidirectional"))
    )
    (net (code "98") (name "unconnected-(U$3A-GPIO_37-PadP8.22)") (class "Default")
      (node (ref "U$3") (pin "P8.22") (pinfunction "GPIO_37_P8.22") (pintype "bidirectional"))
    )
    (net (code "99") (name "unconnected-(U$3A-GPIO_38-PadP8.3)") (class "Default")
      (node (ref "U$3") (pin "P8.3") (pinfunction "GPIO_38_P8.3") (pintype "bidirectional"))
    )
    (net (code "100") (name "unconnected-(U$3A-GPIO_39-PadP8.4)") (class "Default")
      (node (ref "U$3") (pin "P8.4") (pinfunction "GPIO_39_P8.4") (pintype "bidirectional"))
    )
    (net (code "101") (name "unconnected-(U$3A-GPIO_46-PadP8.16)") (class "Default")
      (node (ref "U$3") (pin "P8.16") (pinfunction "GPIO_46_P8.16") (pintype "bidirectional"))
    )
    (net (code "102") (name "unconnected-(U$3A-GPIO_47-PadP8.15)") (class "Default")
      (node (ref "U$3") (pin "P8.15") (pinfunction "GPIO_47_P8.15") (pintype "bidirectional"))
    )
    (net (code "103") (name "unconnected-(U$3A-GPIO_61-PadP8.26)") (class "Default")
      (node (ref "U$3") (pin "P8.26") (pinfunction "GPIO_61_P8.26") (pintype "bidirectional"))
    )
    (net (code "104") (name "unconnected-(U$3A-GPIO_62-PadP8.21)") (class "Default")
      (node (ref "U$3") (pin "P8.21") (pinfunction "GPIO_62_P8.21") (pintype "bidirectional"))
    )
    (net (code "105") (name "unconnected-(U$3A-GPIO_63-PadP8.20)") (class "Default")
      (node (ref "U$3") (pin "P8.20") (pinfunction "GPIO_63_P8.20") (pintype "bidirectional"))
    )
    (net (code "106") (name "unconnected-(U$3A-GPIO_65-PadP8.18)") (class "Default")
      (node (ref "U$3") (pin "P8.18") (pinfunction "GPIO_65_P8.18") (pintype "bidirectional"))
    )
    (net (code "107") (name "unconnected-(U$3A-GPIO_66-PadP8.7)") (class "Default")
      (node (ref "U$3") (pin "P8.7") (pinfunction "GPIO_66_P8.7") (pintype "bidirectional"))
    )
    (net (code "108") (name "unconnected-(U$3A-GPIO_67-PadP8.8)") (class "Default")
      (node (ref "U$3") (pin "P8.8") (pinfunction "GPIO_67_P8.8") (pintype "bidirectional"))
    )
    (net (code "109") (name "unconnected-(U$3A-GPIO_68-PadP8.10)") (class "Default")
      (node (ref "U$3") (pin "P8.10") (pinfunction "GPIO_68_P8.10") (pintype "bidirectional"))
    )
    (net (code "110") (name "unconnected-(U$3A-GPIO_69-PadP8.9)") (class "Default")
      (node (ref "U$3") (pin "P8.9") (pinfunction "GPIO_69_P8.9") (pintype "bidirectional"))
    )
    (net (code "111") (name "unconnected-(U$3B-AIN0-PadP9.39)") (class "Default")
      (node (ref "U$3") (pin "P9.39") (pinfunction "AIN0_P9.39") (pintype "bidirectional"))
    )
    (net (code "112") (name "unconnected-(U$3B-AIN1-PadP9.40)") (class "Default")
      (node (ref "U$3") (pin "P9.40") (pinfunction "AIN1_P9.40") (pintype "bidirectional"))
    )
    (net (code "113") (name "unconnected-(U$3B-AIN2-PadP9.37)") (class "Default")
      (node (ref "U$3") (pin "P9.37") (pinfunction "AIN2_P9.37") (pintype "bidirectional"))
    )
    (net (code "114") (name "unconnected-(U$3B-AIN3-PadP9.38)") (class "Default")
      (node (ref "U$3") (pin "P9.38") (pinfunction "AIN3_P9.38") (pintype "bidirectional"))
    )
    (net (code "115") (name "unconnected-(U$3B-AIN4-PadP9.33)") (class "Default")
      (node (ref "U$3") (pin "P9.33") (pinfunction "AIN4_P9.33") (pintype "bidirectional"))
    )
    (net (code "116") (name "unconnected-(U$3B-AIN5-PadP9.36)") (class "Default")
      (node (ref "U$3") (pin "P9.36") (pinfunction "AIN5_P9.36") (pintype "bidirectional"))
    )
    (net (code "117") (name "unconnected-(U$3B-AIN6-PadP9.35)") (class "Default")
      (node (ref "U$3") (pin "P9.35") (pinfunction "AIN6_P9.35") (pintype "bidirectional"))
    )
    (net (code "118") (name "unconnected-(U$3B-DGND-PadP9.43)") (class "Default")
      (node (ref "U$3") (pin "P9.43") (pinfunction "DGND_P9.43") (pintype "bidirectional"))
    )
    (net (code "119") (name "unconnected-(U$3B-DGND-PadP9.44)") (class "Default")
      (node (ref "U$3") (pin "P9.44") (pinfunction "DGND_P9.44") (pintype "bidirectional"))
    )
    (net (code "120") (name "unconnected-(U$3B-DGND-PadP9.45)") (class "Default")
      (node (ref "U$3") (pin "P9.45") (pinfunction "DGND_P9.45") (pintype "bidirectional"))
    )
    (net (code "121") (name "unconnected-(U$3B-DGND-PadP9.46)") (class "Default")
      (node (ref "U$3") (pin "P9.46") (pinfunction "DGND_P9.46") (pintype "bidirectional"))
    )
    (net (code "122") (name "unconnected-(U$3B-GNDA_ADC-PadP9.34)") (class "Default")
      (node (ref "U$3") (pin "P9.34") (pinfunction "GNDA_ADC_P9.34") (pintype "bidirectional"))
    )
    (net (code "123") (name "unconnected-(U$3B-GPIO_7-PadP9.42)") (class "Default")
      (node (ref "U$3") (pin "P9.42") (pinfunction "GPIO_7_P9.42") (pintype "bidirectional"))
    )
    (net (code "124") (name "unconnected-(U$3B-GPIO_20-PadP9.41)") (class "Default")
      (node (ref "U$3") (pin "P9.41") (pinfunction "GPIO_20_P9.41") (pintype "bidirectional"))
    )
    (net (code "125") (name "unconnected-(U$3B-GPIO_30-PadP9.11)") (class "Default")
      (node (ref "U$3") (pin "P9.11") (pinfunction "GPIO_30_P9.11") (pintype "bidirectional"))
    )
    (net (code "126") (name "unconnected-(U$3B-GPIO_31-PadP9.13)") (class "Default")
      (node (ref "U$3") (pin "P9.13") (pinfunction "GPIO_31_P9.13") (pintype "bidirectional"))
    )
    (net (code "127") (name "unconnected-(U$3B-GPIO_40-PadP9.14)") (class "Default")
      (node (ref "U$3") (pin "P9.14") (pinfunction "GPIO_40_P9.14") (pintype "bidirectional"))
    )
    (net (code "128") (name "unconnected-(U$3B-GPIO_48-PadP9.15)") (class "Default")
      (node (ref "U$3") (pin "P9.15") (pinfunction "GPIO_48_P9.15") (pintype "bidirectional"))
    )
    (net (code "129") (name "unconnected-(U$3B-GPIO_49-PadP9.23)") (class "Default")
      (node (ref "U$3") (pin "P9.23") (pinfunction "GPIO_49_P9.23") (pintype "bidirectional"))
    )
    (net (code "130") (name "unconnected-(U$3B-GPIO_51-PadP9.16)") (class "Default")
      (node (ref "U$3") (pin "P9.16") (pinfunction "GPIO_51_P9.16") (pintype "bidirectional"))
    )
    (net (code "131") (name "unconnected-(U$3B-GPIO_60-PadP9.12)") (class "Default")
      (node (ref "U$3") (pin "P9.12") (pinfunction "GPIO_60_P9.12") (pintype "bidirectional"))
    )
    (net (code "132") (name "unconnected-(U$3B-PWR_BUT-PadP9.9)") (class "Default")
      (node (ref "U$3") (pin "P9.9") (pinfunction "PWR_BUT_P9.9") (pintype "bidirectional"))
    )
    (net (code "133") (name "unconnected-(U$3B-SYS_5V-PadP9.7)") (class "Default")
      (node (ref "U$3") (pin "P9.7") (pinfunction "SYS_5V_P9.7") (pintype "bidirectional"))
    )
    (net (code "134") (name "unconnected-(U$3B-SYS_5V-PadP9.8)") (class "Default")
      (node (ref "U$3") (pin "P9.8") (pinfunction "SYS_5V_P9.8") (pintype "bidirectional"))
    )
    (net (code "135") (name "unconnected-(U$3B-SYS_RESET~{N}-PadP9.10)") (class "Default")
      (node (ref "U$3") (pin "P9.10") (pinfunction "SYS_RESET~{N}_P9.10") (pintype "bidirectional"))
    )
    (net (code "136") (name "unconnected-(U$3B-VDD_3V3-PadP9.3)") (class "Default")
      (node (ref "U$3") (pin "P9.3") (pinfunction "VDD_3V3_P9.3") (pintype "bidirectional"))
    )
    (net (code "137") (name "unconnected-(U$3B-VDD_3V3-PadP9.4)") (class "Default")
      (node (ref "U$3") (pin "P9.4") (pinfunction "VDD_3V3_P9.4") (pintype "bidirectional"))
    )
    (net (code "138") (name "unconnected-(U$3B-VDD_5V-PadP9.5)") (class "Default")
      (node (ref "U$3") (pin "P9.5") (pinfunction "VDD_5V_P9.5") (pintype "bidirectional"))
    )
    (net (code "139") (name "unconnected-(U$3B-VDD_5V-PadP9.6)") (class "Default")
      (node (ref "U$3") (pin "P9.6") (pinfunction "VDD_5V_P9.6") (pintype "bidirectional"))
    )
    (net (code "140") (name "unconnected-(U$3B-VDD_ADC-PadP9.32)") (class "Default")
      (node (ref "U$3") (pin "P9.32") (pinfunction "VDD_ADC_P9.32") (pintype "bidirectional"))
    )
    (net (code "141") (name "unconnected-(U1-RA2-Pad6)") (class "Default")
      (node (ref "U1") (pin "6") (pinfunction "RA2_6") (pintype "bidirectional"))
    )
    (net (code "142") (name "unconnected-(U1-RA3-Pad7)") (class "Default")
      (node (ref "U1") (pin "7") (pinfunction "RA3_7") (pintype "bidirectional"))
    )
    (net (code "143") (name "unconnected-(U1-RA4-Pad9)") (class "Default")
      (node (ref "U1") (pin "9") (pinfunction "RA4_9") (pintype "bidirectional"))
    )
    (net (code "144") (name "unconnected-(U1-RB4-Pad8)") (class "Default")
      (node (ref "U1") (pin "8") (pinfunction "RB4_8") (pintype "bidirectional"))
    )
    (net (code "145") (name "unconnected-(U1-TDI-Pad13)") (class "Default")
      (node (ref "U1") (pin "13") (pinfunction "TDI_13") (pintype "input"))
    )
    (net (code "146") (name "unconnected-(U1-TMS-Pad11)") (class "Default")
      (node (ref "U1") (pin "11") (pinfunction "TMS_11") (pintype "input"))
    )
    (net (code "147") (name "unconnected-(U2-RA2-Pad6)") (class "Default")
      (node (ref "U2") (pin "6") (pinfunction "RA2_6") (pintype "bidirectional"))
    )
    (net (code "148") (name "unconnected-(U2-RA3-Pad7)") (class "Default")
      (node (ref "U2") (pin "7") (pinfunction "RA3_7") (pintype "bidirectional"))
    )
    (net (code "149") (name "unconnected-(U2-RA4-Pad9)") (class "Default")
      (node (ref "U2") (pin "9") (pinfunction "RA4_9") (pintype "bidirectional"))
    )
    (net (code "150") (name "unconnected-(U2-RB13-Pad21)") (class "Default")
      (node (ref "U2") (pin "21") (pinfunction "RB13_21") (pintype "bidirectional"))
    )
    (net (code "151") (name "unconnected-(U2-TMS-Pad11)") (class "Default")
      (node (ref "U2") (pin "11") (pinfunction "TMS_11") (pintype "input"))
    )
    (net (code "152") (name "~{SS}") (class "Default")
      (node (ref "U$3") (pin "P9.17") (pinfunction "GPIO_4_P9.17") (pintype "bidirectional"))
      (node (ref "U1") (pin "18") (pinfunction "RB10_18") (pintype "passive"))
    )
  )
)
